# Sheet1.net
KiCad netlist of a schematic drawn in Altium Designer
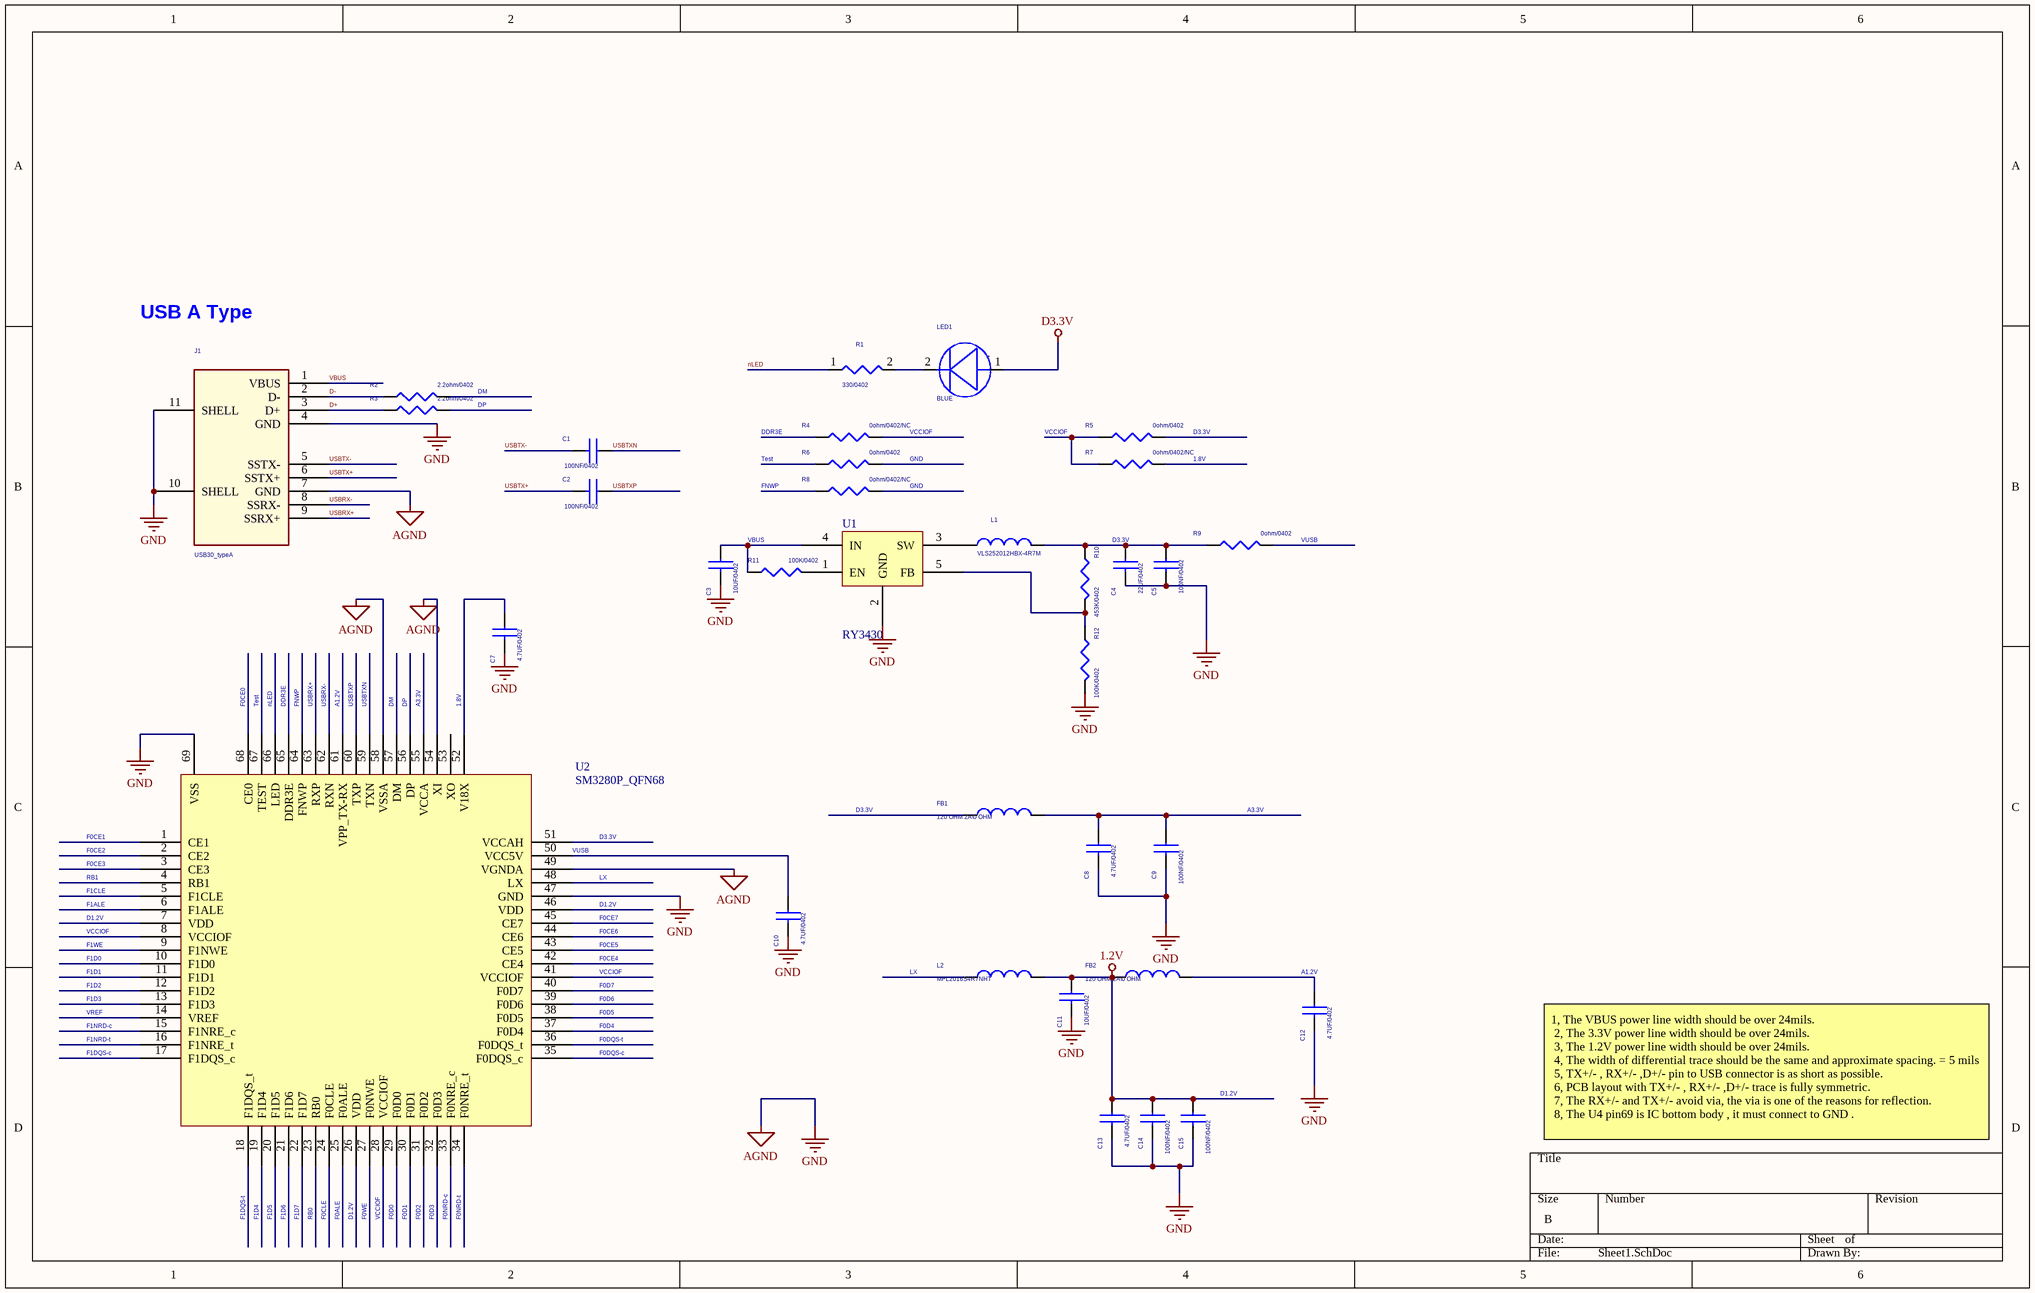
[diagram p0: Sheet1.SchDoc]

(export (version "E")
  (design (tool "Eeschema 10.0.6"))
  (components
    (comp (ref "C1")
      (value "100NF/0402")
      (footprint "C0402")
      (fields
        (field (name "CRITICAL_PART") "N")
        (field (name "MANUFACTURER") "PANASONIC")
        (field (name "PART_NUMBER") "11G10210621R")
      )
      (libsource (lib "*") (part "C0603"))
    )
    (comp (ref "C2")
      (value "100NF/0402")
      (footprint "C0402")
      (fields
        (field (name "CRITICAL_PART") "N")
        (field (name "MANUFACTURER") "PANASONIC")
        (field (name "PART_NUMBER") "11G10210621R")
      )
      (libsource (lib "*") (part "C0603"))
    )
    (comp (ref "C3")
      (value "10UF/0402")
      (footprint "C0402")
      (fields
        (field (name "CRITICAL_PART") "N")
        (field (name "MANUFACTURER") "PANASONIC")
        (field (name "PART_NUMBER") "11G10210621R")
      )
      (libsource (lib "*") (part "C0603"))
    )
    (comp (ref "C4")
      (value "22UF/0402")
      (footprint "C0402")
      (fields
        (field (name "CRITICAL_PART") "N")
        (field (name "MANUFACTURER") "PANASONIC")
        (field (name "PART_NUMBER") "11G10210621R")
      )
      (libsource (lib "*") (part "C0603"))
    )
    (comp (ref "C5")
      (value "100NF/0402")
      (footprint "C0402")
      (fields
        (field (name "CRITICAL_PART") "N")
        (field (name "MANUFACTURER") "PANASONIC")
        (field (name "PART_NUMBER") "11G10210621R")
      )
      (libsource (lib "*") (part "C0603"))
    )
    (comp (ref "C7")
      (value "4.7UF/0402")
      (footprint "C0402")
      (fields
        (field (name "CRITICAL_PART") "N")
        (field (name "MANUFACTURER") "PANASONIC")
        (field (name "PART_NUMBER") "11G10210621R")
      )
      (libsource (lib "*") (part "C0603"))
    )
    (comp (ref "C8")
      (value "4.7UF/0402")
      (footprint "C0402")
      (fields
        (field (name "CRITICAL_PART") "N")
        (field (name "MANUFACTURER") "PANASONIC")
        (field (name "PART_NUMBER") "11G10210621R")
      )
      (libsource (lib "*") (part "C0603"))
    )
    (comp (ref "C9")
      (value "100NF/0402")
      (footprint "C0402")
      (fields
        (field (name "TOLERANCE") "+80/-20%")
        (field (name "PART_NUMBER") "11G101104340")
        (field (name "MANUFACTURER") "WALSIN")
      )
      (libsource (lib "*") (part "C0402_Dup1"))
    )
    (comp (ref "C10")
      (value "4.7UF/0402")
      (footprint "C0402")
      (fields
        (field (name "CRITICAL_PART") "N")
        (field (name "MANUFACTURER") "PANASONIC")
        (field (name "PART_NUMBER") "11G10210621R")
      )
      (libsource (lib "*") (part "C0603"))
    )
    (comp (ref "C11")
      (value "10UF/0402")
      (footprint "C0402")
      (fields
        (field (name "CRITICAL_PART") "N")
        (field (name "MANUFACTURER") "PANASONIC")
        (field (name "PART_NUMBER") "11G10210621R")
      )
      (libsource (lib "*") (part "C0603"))
    )
    (comp (ref "C12")
      (value "4.7UF/0402")
      (footprint "C0402")
      (fields
        (field (name "CRITICAL_PART") "N")
        (field (name "MANUFACTURER") "PANASONIC")
        (field (name "PART_NUMBER") "11G10210621R")
      )
      (libsource (lib "*") (part "C0603"))
    )
    (comp (ref "C13")
      (value "4.7UF/0402")
      (footprint "C0402")
      (fields
        (field (name "CRITICAL_PART") "N")
        (field (name "MANUFACTURER") "PANASONIC")
        (field (name "PART_NUMBER") "11G10210621R")
      )
      (libsource (lib "*") (part "C0603"))
    )
    (comp (ref "C14")
      (value "100NF/0402")
      (footprint "C0201")
      (fields
        (field (name "TOLERANCE") "+80/-20%")
        (field (name "PART_NUMBER") "11G101104340")
        (field (name "MANUFACTURER") "WALSIN")
      )
      (libsource (lib "*") (part "C0402_Dup1"))
    )
    (comp (ref "C15")
      (value "100NF/0402")
      (footprint "C0402")
      (fields
        (field (name "TOLERANCE") "+80/-20%")
        (field (name "PART_NUMBER") "11G101104340")
        (field (name "MANUFACTURER") "WALSIN")
      )
      (libsource (lib "*") (part "C0402_Dup1"))
    )
    (comp (ref "FB1")
      (value "120 OHM 2~{A}0 OHM")
      (footprint "SL0402")
      (description "FB SMD 120 OHM 2A 0402")
      (fields (field (name "PART NUMBER") "09G102000160") (field (name "MANUFACTURER") "MURATA"))
      (libsource (lib "*") (part "FB0603"))
    )
    (comp (ref "FB2")
      (value "120 OHM 2~{A}0 OHM")
      (footprint "SL0402")
      (description "FB SMD 120 OHM 2A 0402")
      (fields (field (name "PART NUMBER") "09G102000160") (field (name "MANUFACTURER") "MURATA"))
      (libsource (lib "*") (part "FB0603"))
    )
    (comp (ref "J1")
      (value "USB30_typeA")
      (footprint "USB-3.0AAAA")
      (libsource (lib "*") (part "USB30 connector_0"))
    )
    (comp (ref "L1")
      (value "VLS252012HBX-4R7M")
      (footprint "L2520")
      (fields
        (field (name "CRITICAL_PART") "N")
        (field (name "MANUFACTURER") "GOTREND")
        (field (name "PART_NUMBER") "09G1502034A0")
      )
      (libsource (lib "*") (part "GNR2512PA-1R0M_0"))
    )
    (comp (ref "L2")
      (value "MPL2016S4R7NHT")
      (footprint "L2016")
      (fields
        (field (name "PART NUMBER") "09G102000160")
        (field (name "MANUFACTURER") "MURATA")
        (field (name "CRITICAL_PART") "N")
      )
      (libsource (lib "*") (part "FB0603"))
    )
    (comp (ref "LED1")
      (value "BLUE")
      (footprint "LED0603")
      (fields (field (name "PART NUMBER") "07G015200206") (field (name "CRITICAL_PART") "N"))
      (libsource (lib "*") (part "LED"))
    )
    (comp (ref "R1")
      (value "330/0402")
      (footprint "R0402")
      (fields
        (field (name "CRITICAL_PART") "N")
        (field (name "TOLERANCE") "5%")
        (field (name "PART NUMBER") "10G212102004010")
        (field (name "SYMBOL_PREVIEW") "http://tp-caevm-01/ET_Test/FpPre.aspx?PN=10G212102004010&LIB=COM")
      )
      (libsource (lib "*") (part "R_Dup1"))
    )
    (comp (ref "R2") (value "2.2ohm/0402") (footprint "R0402") (libsource (lib "*") (part "R")))
    (comp (ref "R3") (value "2.2ohm/0402") (footprint "R0402") (libsource (lib "*") (part "R")))
    (comp (ref "R4") (value "0ohm/0402/NC") (footprint "R0201") (libsource (lib "*") (part "R")))
    (comp (ref "R5") (value "0ohm/0402") (footprint "R0201") (libsource (lib "*") (part "R")))
    (comp (ref "R6") (value "0ohm/0402") (footprint "R0201") (libsource (lib "*") (part "R")))
    (comp (ref "R7") (value "0ohm/0402/NC") (footprint "R0201") (libsource (lib "*") (part "R")))
    (comp (ref "R8") (value "0ohm/0402/NC") (footprint "R0201") (libsource (lib "*") (part "R")))
    (comp (ref "R9") (value "0ohm/0402") (footprint "R0201") (libsource (lib "*") (part "R")))
    (comp (ref "R10")
      (value "453K/0402")
      (footprint "R0402")
      (fields
        (field (name "CRITICAL_PART") "N")
        (field (name "MANUFACTURER") "WALSIN")
        (field (name "PART_NUMBER") "10G101010410")
      )
      (libsource (lib "*") (part "R0402"))
    )
    (comp (ref "R11")
      (value "100K/0402")
      (footprint "R0402")
      (fields
        (field (name "CRITICAL_PART") "N")
        (field (name "MANUFACTURER") "WALSIN")
        (field (name "PART_NUMBER") "10G101010410")
      )
      (libsource (lib "*") (part "R0402"))
    )
    (comp (ref "R12")
      (value "100K/0402")
      (footprint "R0402")
      (fields
        (field (name "CRITICAL_PART") "N")
        (field (name "MANUFACTURER") "WALSIN")
        (field (name "PART_NUMBER") "10G101010410")
      )
      (libsource (lib "*") (part "R0402"))
    )
    (comp (ref "U1") (value "RY3430") (libsource (lib "Schlib1") (part "RY3430")))
    (comp (ref "U2") (value "SM3280P_QFN68") (libsource (lib "Schlib1") (part "SM3280P_QFN68")))
  )
  (nets
    (net (code "1") (name "/1.8V") (class "Default")
      (node (ref "C7") (pin "1") (pinfunction "1_1") (pintype "passive"))
      (node (ref "R7") (pin "2") (pinfunction "2_2") (pintype "passive"))
      (node (ref "U2") (pin "52") (pinfunction "V18X_52") (pintype "passive"))
    )
    (net (code "2") (name "/A1.2V") (class "Default")
      (node (ref "C12") (pin "1") (pinfunction "1_1") (pintype "passive"))
      (node (ref "FB2") (pin "2") (pinfunction "2_2") (pintype "passive"))
      (node (ref "U2") (pin "61") (pinfunction "VPP_TX-RX_61") (pintype "passive"))
    )
    (net (code "3") (name "/A3.3V") (class "Default")
      (node (ref "C8") (pin "1") (pinfunction "1_1") (pintype "passive"))
      (node (ref "C9") (pin "1") (pinfunction "1_1") (pintype "passive"))
      (node (ref "FB1") (pin "2") (pinfunction "2_2") (pintype "passive"))
      (node (ref "U2") (pin "55") (pinfunction "VCCA_55") (pintype "passive"))
    )
    (net (code "4") (name "/D+") (class "Default")
      (node (ref "J1") (pin "3") (pinfunction "D+_3") (pintype "passive"))
      (node (ref "R3") (pin "1") (pinfunction "1_1") (pintype "passive"))
    )
    (net (code "5") (name "/D-") (class "Default")
      (node (ref "J1") (pin "2") (pinfunction "D-_2") (pintype "passive"))
      (node (ref "R2") (pin "1") (pinfunction "1_1") (pintype "passive"))
    )
    (net (code "6") (name "/DDR3E") (class "Default")
      (node (ref "R4") (pin "1") (pinfunction "1_1") (pintype "passive"))
      (node (ref "U2") (pin "65") (pinfunction "DDR3E_65") (pintype "passive"))
    )
    (net (code "7") (name "/DM") (class "Default")
      (node (ref "R2") (pin "2") (pinfunction "2_2") (pintype "passive"))
      (node (ref "U2") (pin "57") (pinfunction "DM_57") (pintype "passive"))
    )
    (net (code "8") (name "/DP") (class "Default")
      (node (ref "R3") (pin "2") (pinfunction "2_2") (pintype "passive"))
      (node (ref "U2") (pin "56") (pinfunction "DP_56") (pintype "passive"))
    )
    (net (code "9") (name "/F0ALE") (class "Default")
      (node (ref "U2") (pin "25") (pinfunction "F0ALE_25") (pintype "passive"))
    )
    (net (code "10") (name "/F0CE0") (class "Default")
      (node (ref "U2") (pin "68") (pinfunction "CE0_68") (pintype "passive"))
    )
    (net (code "11") (name "/F0CE1") (class "Default")
      (node (ref "U2") (pin "1") (pinfunction "CE1_1") (pintype "passive"))
    )
    (net (code "12") (name "/F0CE2") (class "Default")
      (node (ref "U2") (pin "2") (pinfunction "CE2_2") (pintype "passive"))
    )
    (net (code "13") (name "/F0CE3") (class "Default")
      (node (ref "U2") (pin "3") (pinfunction "CE3_3") (pintype "passive"))
    )
    (net (code "14") (name "/F0CE4") (class "Default")
      (node (ref "U2") (pin "42") (pinfunction "CE4_42") (pintype "passive"))
    )
    (net (code "15") (name "/F0CE5") (class "Default")
      (node (ref "U2") (pin "43") (pinfunction "CE5_43") (pintype "passive"))
    )
    (net (code "16") (name "/F0CE6") (class "Default")
      (node (ref "U2") (pin "44") (pinfunction "CE6_44") (pintype "passive"))
    )
    (net (code "17") (name "/F0CE7") (class "Default")
      (node (ref "U2") (pin "45") (pinfunction "CE7_45") (pintype "passive"))
    )
    (net (code "18") (name "/F0CLE") (class "Default")
      (node (ref "U2") (pin "24") (pinfunction "F0CLE_24") (pintype "passive"))
    )
    (net (code "19") (name "/F0D0") (class "Default")
      (node (ref "U2") (pin "29") (pinfunction "F0D0_29") (pintype "passive"))
    )
    (net (code "20") (name "/F0D1") (class "Default")
      (node (ref "U2") (pin "30") (pinfunction "F0D1_30") (pintype "passive"))
    )
    (net (code "21") (name "/F0D2") (class "Default")
      (node (ref "U2") (pin "31") (pinfunction "F0D2_31") (pintype "passive"))
    )
    (net (code "22") (name "/F0D3") (class "Default")
      (node (ref "U2") (pin "32") (pinfunction "F0D3_32") (pintype "passive"))
    )
    (net (code "23") (name "/F0D4") (class "Default")
      (node (ref "U2") (pin "37") (pinfunction "F0D4_37") (pintype "passive"))
    )
    (net (code "24") (name "/F0D5") (class "Default")
      (node (ref "U2") (pin "38") (pinfunction "F0D5_38") (pintype "passive"))
    )
    (net (code "25") (name "/F0D6") (class "Default")
      (node (ref "U2") (pin "39") (pinfunction "F0D6_39") (pintype "passive"))
    )
    (net (code "26") (name "/F0D7") (class "Default")
      (node (ref "U2") (pin "40") (pinfunction "F0D7_40") (pintype "passive"))
    )
    (net (code "27") (name "/F0DQS-c") (class "Default")
      (node (ref "U2") (pin "35") (pinfunction "F0DQS_c_35") (pintype "passive"))
    )
    (net (code "28") (name "/F0DQS-t") (class "Default")
      (node (ref "U2") (pin "36") (pinfunction "F0DQS_t_36") (pintype "passive"))
    )
    (net (code "29") (name "/F0NRD-c") (class "Default")
      (node (ref "U2") (pin "33") (pinfunction "F0NRE_c_33") (pintype "passive"))
    )
    (net (code "30") (name "/F0NRD-t") (class "Default")
      (node (ref "U2") (pin "34") (pinfunction "F0NRE_t_34") (pintype "passive"))
    )
    (net (code "31") (name "/F0WE") (class "Default")
      (node (ref "U2") (pin "27") (pinfunction "F0NWE_27") (pintype "passive"))
    )
    (net (code "32") (name "/F1ALE") (class "Default")
      (node (ref "U2") (pin "6") (pinfunction "F1ALE_6") (pintype "passive"))
    )
    (net (code "33") (name "/F1CLE") (class "Default")
      (node (ref "U2") (pin "5") (pinfunction "F1CLE_5") (pintype "passive"))
    )
    (net (code "34") (name "/F1D0") (class "Default")
      (node (ref "U2") (pin "10") (pinfunction "F1D0_10") (pintype "passive"))
    )
    (net (code "35") (name "/F1D1") (class "Default")
      (node (ref "U2") (pin "11") (pinfunction "F1D1_11") (pintype "passive"))
    )
    (net (code "36") (name "/F1D2") (class "Default")
      (node (ref "U2") (pin "12") (pinfunction "F1D2_12") (pintype "passive"))
    )
    (net (code "37") (name "/F1D3") (class "Default")
      (node (ref "U2") (pin "13") (pinfunction "F1D3_13") (pintype "passive"))
    )
    (net (code "38") (name "/F1D4") (class "Default")
      (node (ref "U2") (pin "19") (pinfunction "F1D4_19") (pintype "passive"))
    )
    (net (code "39") (name "/F1D5") (class "Default")
      (node (ref "U2") (pin "20") (pinfunction "F1D5_20") (pintype "passive"))
    )
    (net (code "40") (name "/F1D6") (class "Default")
      (node (ref "U2") (pin "21") (pinfunction "F1D6_21") (pintype "passive"))
    )
    (net (code "41") (name "/F1D7") (class "Default")
      (node (ref "U2") (pin "22") (pinfunction "F1D7_22") (pintype "passive"))
    )
    (net (code "42") (name "/F1DQS-c") (class "Default")
      (node (ref "U2") (pin "17") (pinfunction "F1DQS_c_17") (pintype "passive"))
    )
    (net (code "43") (name "/F1DQS-t") (class "Default")
      (node (ref "U2") (pin "18") (pinfunction "F1DQS_t_18") (pintype "passive"))
    )
    (net (code "44") (name "/F1NRD-c") (class "Default")
      (node (ref "U2") (pin "15") (pinfunction "F1NRE_c_15") (pintype "passive"))
    )
    (net (code "45") (name "/F1NRD-t") (class "Default")
      (node (ref "U2") (pin "16") (pinfunction "F1NRE_t_16") (pintype "passive"))
    )
    (net (code "46") (name "/F1WE") (class "Default")
      (node (ref "U2") (pin "9") (pinfunction "F1NWE_9") (pintype "passive"))
    )
    (net (code "47") (name "/FNWP") (class "Default")
      (node (ref "R8") (pin "1") (pinfunction "1_1") (pintype "passive"))
      (node (ref "U2") (pin "64") (pinfunction "FNWP_64") (pintype "passive"))
    )
    (net (code "48") (name "/LX") (class "Default")
      (node (ref "L2") (pin "1") (pinfunction "1_1") (pintype "passive"))
      (node (ref "U2") (pin "48") (pinfunction "LX_48") (pintype "passive"))
    )
    (net (code "49") (name "/RB0") (class "Default")
      (node (ref "U2") (pin "23") (pinfunction "RB0_23") (pintype "passive"))
    )
    (net (code "50") (name "/RB1") (class "Default")
      (node (ref "U2") (pin "4") (pinfunction "RB1_4") (pintype "passive"))
    )
    (net (code "51") (name "/Test") (class "Default")
      (node (ref "R6") (pin "1") (pinfunction "1_1") (pintype "passive"))
      (node (ref "U2") (pin "67") (pinfunction "TEST_67") (pintype "passive"))
    )
    (net (code "52") (name "/USBRX+") (class "Default")
      (node (ref "J1") (pin "9") (pinfunction "SSRX+_9") (pintype "passive"))
      (node (ref "U2") (pin "63") (pinfunction "RXP_63") (pintype "passive"))
    )
    (net (code "53") (name "/USBRX-") (class "Default")
      (node (ref "J1") (pin "8") (pinfunction "SSRX-_8") (pintype "passive"))
      (node (ref "U2") (pin "62") (pinfunction "RXN_62") (pintype "passive"))
    )
    (net (code "54") (name "/USBTX+") (class "Default")
      (node (ref "C2") (pin "2") (pinfunction "2_2") (pintype "passive"))
      (node (ref "J1") (pin "6") (pinfunction "SSTX+_6") (pintype "passive"))
    )
    (net (code "55") (name "/USBTX-") (class "Default")
      (node (ref "C1") (pin "2") (pinfunction "2_2") (pintype "passive"))
      (node (ref "J1") (pin "5") (pinfunction "SSTX-_5") (pintype "passive"))
    )
    (net (code "56") (name "/USBTXN") (class "Default")
      (node (ref "C1") (pin "1") (pinfunction "1_1") (pintype "passive"))
      (node (ref "U2") (pin "59") (pinfunction "TXN_59") (pintype "passive"))
    )
    (net (code "57") (name "/USBTXP") (class "Default")
      (node (ref "C2") (pin "1") (pinfunction "1_1") (pintype "passive"))
      (node (ref "U2") (pin "60") (pinfunction "TXP_60") (pintype "passive"))
    )
    (net (code "58") (name "/VBUS") (class "Default")
      (node (ref "C3") (pin "1") (pinfunction "1_1") (pintype "passive"))
      (node (ref "J1") (pin "1") (pinfunction "VBUS_1") (pintype "passive"))
      (node (ref "R11") (pin "1") (pinfunction "1_1") (pintype "passive"))
      (node (ref "U1") (pin "4") (pinfunction "IN_4") (pintype "passive"))
    )
    (net (code "59") (name "/VCCIOF") (class "Default")
      (node (ref "R4") (pin "2") (pinfunction "2_2") (pintype "passive"))
      (node (ref "R5") (pin "1") (pinfunction "1_1") (pintype "passive"))
      (node (ref "R7") (pin "1") (pinfunction "1_1") (pintype "passive"))
      (node (ref "U2") (pin "28") (pinfunction "VCCIOF_28") (pintype "passive"))
      (node (ref "U2") (pin "41") (pinfunction "VCCIOF_41") (pintype "passive"))
      (node (ref "U2") (pin "8") (pinfunction "VCCIOF_8") (pintype "passive"))
    )
    (net (code "60") (name "/VREF") (class "Default")
      (node (ref "U2") (pin "14") (pinfunction "VREF_14") (pintype "passive"))
    )
    (net (code "61") (name "/VUSB") (class "Default")
      (node (ref "C10") (pin "1") (pinfunction "1_1") (pintype "passive"))
      (node (ref "R9") (pin "2") (pinfunction "2_2") (pintype "passive"))
      (node (ref "U2") (pin "50") (pinfunction "VCC5V_50") (pintype "passive"))
    )
    (net (code "62") (name "/nLED") (class "Default")
      (node (ref "R1") (pin "1") (pinfunction "1_1") (pintype "passive"))
      (node (ref "U2") (pin "66") (pinfunction "LED_66") (pintype "passive"))
    )
    (net (code "63") (name "1.2V") (class "Default")
      (node (ref "C11") (pin "1") (pinfunction "1_1") (pintype "passive"))
      (node (ref "C13") (pin "1") (pinfunction "1_1") (pintype "passive"))
      (node (ref "C14") (pin "1") (pinfunction "1_1") (pintype "passive"))
      (node (ref "C15") (pin "1") (pinfunction "1_1") (pintype "passive"))
      (node (ref "FB2") (pin "1") (pinfunction "1_1") (pintype "passive"))
      (node (ref "L2") (pin "2") (pinfunction "2_2") (pintype "passive"))
      (node (ref "U2") (pin "26") (pinfunction "VDD_26") (pintype "passive"))
      (node (ref "U2") (pin "46") (pinfunction "VDD_46") (pintype "passive"))
      (node (ref "U2") (pin "7") (pinfunction "VDD_7") (pintype "passive"))
    )
    (net (code "64") (name "AGND") (class "Default")
      (node (ref "C10") (pin "2") (pinfunction "2_2") (pintype "passive"))
      (node (ref "C11") (pin "2") (pinfunction "2_2") (pintype "passive"))
      (node (ref "C12") (pin "2") (pinfunction "2_2") (pintype "passive"))
      (node (ref "C13") (pin "2") (pinfunction "2_2") (pintype "passive"))
      (node (ref "C14") (pin "2") (pinfunction "2_2") (pintype "passive"))
      (node (ref "C15") (pin "2") (pinfunction "2_2") (pintype "passive"))
      (node (ref "C3") (pin "2") (pinfunction "2_2") (pintype "passive"))
      (node (ref "C4") (pin "2") (pinfunction "2_2") (pintype "passive"))
      (node (ref "C5") (pin "2") (pinfunction "2_2") (pintype "passive"))
      (node (ref "C7") (pin "2") (pinfunction "2_2") (pintype "passive"))
      (node (ref "C8") (pin "2") (pinfunction "2_2") (pintype "passive"))
      (node (ref "C9") (pin "2") (pinfunction "2_2") (pintype "passive"))
      (node (ref "J1") (pin "10") (pinfunction "SHELL_10") (pintype "passive"))
      (node (ref "J1") (pin "11") (pinfunction "SHELL_11") (pintype "passive"))
      (node (ref "J1") (pin "4") (pinfunction "GND_4") (pintype "passive"))
      (node (ref "J1") (pin "7") (pinfunction "GND_7") (pintype "passive"))
      (node (ref "R12") (pin "2") (pinfunction "2_2") (pintype "passive"))
      (node (ref "R6") (pin "2") (pinfunction "2_2") (pintype "passive"))
      (node (ref "R8") (pin "2") (pinfunction "2_2") (pintype "passive"))
      (node (ref "U1") (pin "2") (pinfunction "GND_2") (pintype "passive"))
      (node (ref "U2") (pin "47") (pinfunction "GND_47") (pintype "passive"))
      (node (ref "U2") (pin "49") (pinfunction "VGNDA_49") (pintype "passive"))
      (node (ref "U2") (pin "54") (pinfunction "XI_54") (pintype "passive"))
      (node (ref "U2") (pin "58") (pinfunction "VSSA_58") (pintype "passive"))
      (node (ref "U2") (pin "69") (pinfunction "VSS_69") (pintype "passive"))
    )
    (net (code "65") (name "D3.3V") (class "Default")
      (node (ref "C4") (pin "1") (pinfunction "1_1") (pintype "passive"))
      (node (ref "C5") (pin "1") (pinfunction "1_1") (pintype "passive"))
      (node (ref "FB1") (pin "1") (pinfunction "1_1") (pintype "passive"))
      (node (ref "L1") (pin "2") (pinfunction "2_2") (pintype "passive"))
      (node (ref "LED1") (pin "1") (pinfunction "ANODE_1") (pintype "passive"))
      (node (ref "R10") (pin "1") (pinfunction "1_1") (pintype "passive"))
      (node (ref "R5") (pin "2") (pinfunction "2_2") (pintype "passive"))
      (node (ref "R9") (pin "1") (pinfunction "1_1") (pintype "passive"))
      (node (ref "U2") (pin "51") (pinfunction "VCCAH_51") (pintype "passive"))
    )
    (net (code "66") (name "Net-(LED1-CATHODE)") (class "Default")
      (node (ref "LED1") (pin "2") (pinfunction "CATHODE_2") (pintype "passive"))
      (node (ref "R1") (pin "2") (pinfunction "2_2") (pintype "passive"))
    )
    (net (code "67") (name "Net-(U1-FB)") (class "Default")
      (node (ref "R10") (pin "2") (pinfunction "2_2") (pintype "passive"))
      (node (ref "R12") (pin "1") (pinfunction "1_1") (pintype "passive"))
      (node (ref "U1") (pin "5") (pinfunction "FB_5") (pintype "passive"))
    )
    (net (code "68") (name "Net-(U1-SW)") (class "Default")
      (node (ref "L1") (pin "1") (pinfunction "1_1") (pintype "passive"))
      (node (ref "U1") (pin "3") (pinfunction "SW_3") (pintype "passive"))
    )
    (net (code "69") (name "unconnected-(R11-Pad2)") (class "Default")
      (node (ref "R11") (pin "2") (pinfunction "2_2") (pintype "passive"))
    )
    (net (code "70") (name "unconnected-(U1-EN-Pad1)") (class "Default")
      (node (ref "U1") (pin "1") (pinfunction "EN_1") (pintype "passive"))
    )
    (net (code "71") (name "unconnected-(U2-XO-Pad53)") (class "Default")
      (node (ref "U2") (pin "53") (pinfunction "XO_53") (pintype "passive"))
    )
  )
)
